# icsp.net
KiCad netlist of a schematic drawn in EAGLE
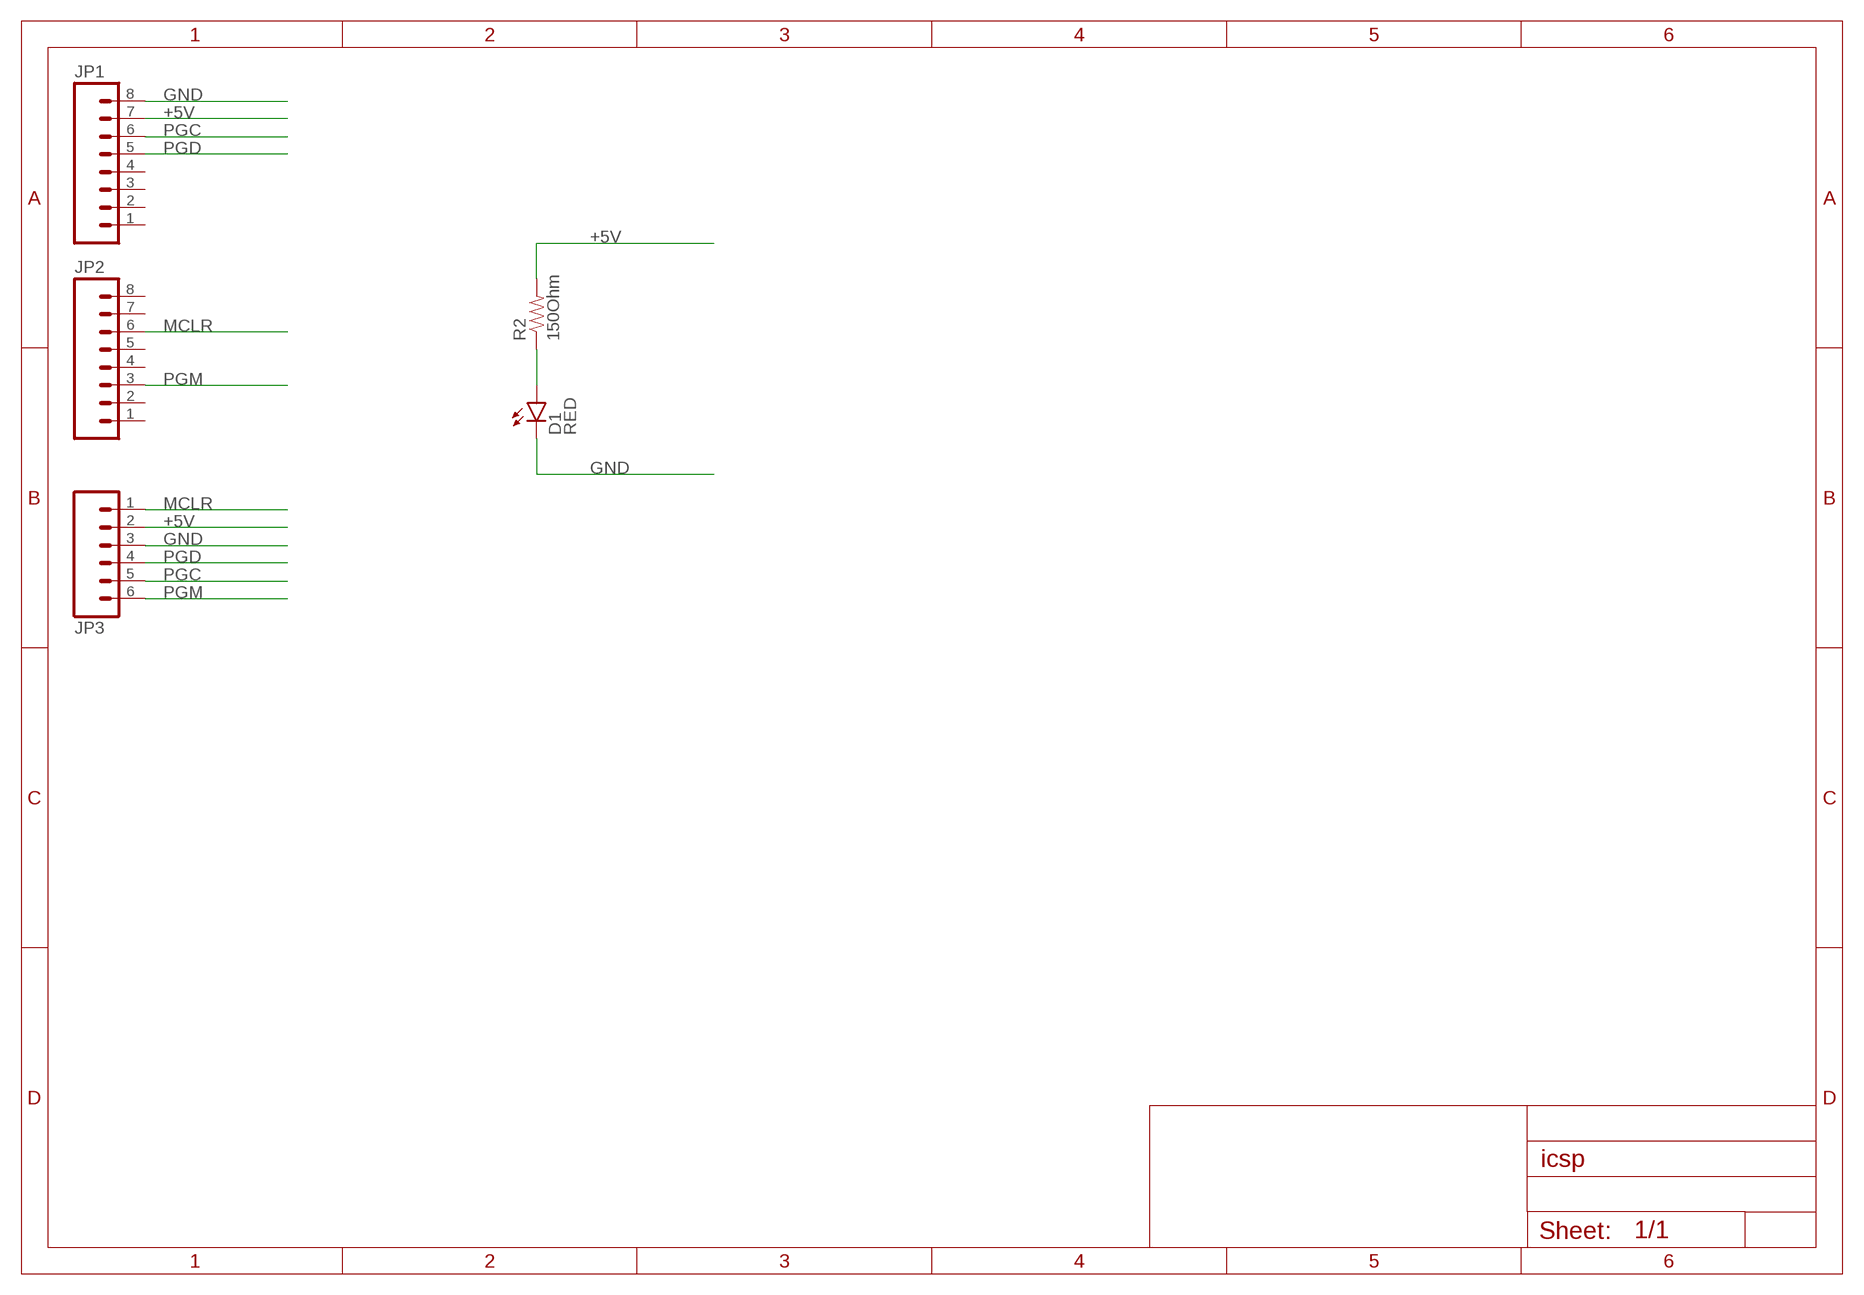
[diagram p0: schematic, sheet 1]

(export (version "E")
  (design (tool "Eeschema 10.0.6"))
  (components
    (comp (ref "D1")
      (value "RED")
      (footprint "eagle-import:LED-0603")
      (libsource (lib "eagle-import") (part "LED-RED0603"))
    )
    (comp (ref "JP1")
      (value "M081X08")
      (footprint "eagle-import:1X08")
      (libsource (lib "eagle-import") (part "M081X08"))
    )
    (comp (ref "JP2")
      (value "M081X08")
      (footprint "eagle-import:1X08")
      (libsource (lib "eagle-import") (part "M081X08"))
    )
    (comp (ref "JP3")
      (value "M06SIP_LOCK")
      (footprint "eagle-import:1X06-SIP_LOCK")
      (libsource (lib "eagle-import") (part "M06SIP_LOCK"))
    )
    (comp (ref "R2")
      (value "150Ohm")
      (footprint "eagle-import:0402-RES")
      (libsource (lib "eagle-import") (part "RESISTOR0402-RES"))
    )
  )
  (nets
    (net (code "1") (name "/+5V") (class "Default")
      (node (ref "JP1") (pin "7") (pinfunction "7_7") (pintype "passive"))
      (node (ref "JP3") (pin "2") (pinfunction "2_2") (pintype "passive"))
      (node (ref "R2") (pin "2") (pinfunction "2_2") (pintype "passive"))
    )
    (net (code "2") (name "/GND") (class "Default")
      (node (ref "D1") (pin "C") (pinfunction "C_C") (pintype "passive"))
      (node (ref "JP1") (pin "8") (pinfunction "8_8") (pintype "passive"))
      (node (ref "JP3") (pin "3") (pinfunction "3_3") (pintype "passive"))
    )
    (net (code "3") (name "/MCLR") (class "Default")
      (node (ref "JP2") (pin "6") (pinfunction "6_6") (pintype "passive"))
      (node (ref "JP3") (pin "1") (pinfunction "1_1") (pintype "passive"))
    )
    (net (code "4") (name "/PGC") (class "Default")
      (node (ref "JP1") (pin "6") (pinfunction "6_6") (pintype "passive"))
      (node (ref "JP3") (pin "5") (pinfunction "5_5") (pintype "passive"))
    )
    (net (code "5") (name "/PGD") (class "Default")
      (node (ref "JP1") (pin "5") (pinfunction "5_5") (pintype "passive"))
      (node (ref "JP3") (pin "4") (pinfunction "4_4") (pintype "passive"))
    )
    (net (code "6") (name "/PGM") (class "Default")
      (node (ref "JP2") (pin "3") (pinfunction "3_3") (pintype "passive"))
      (node (ref "JP3") (pin "6") (pinfunction "6_6") (pintype "passive"))
    )
    (net (code "7") (name "Net-(D1-PadA)") (class "Default")
      (node (ref "D1") (pin "A") (pinfunction "A_A") (pintype "passive"))
      (node (ref "R2") (pin "1") (pinfunction "1_1") (pintype "passive"))
    )
    (net (code "8") (name "unconnected-(JP1-Pad1)") (class "Default")
      (node (ref "JP1") (pin "1") (pinfunction "1_1") (pintype "passive"))
    )
    (net (code "9") (name "unconnected-(JP1-Pad2)") (class "Default")
      (node (ref "JP1") (pin "2") (pinfunction "2_2") (pintype "passive"))
    )
    (net (code "10") (name "unconnected-(JP1-Pad3)") (class "Default")
      (node (ref "JP1") (pin "3") (pinfunction "3_3") (pintype "passive"))
    )
    (net (code "11") (name "unconnected-(JP1-Pad4)") (class "Default")
      (node (ref "JP1") (pin "4") (pinfunction "4_4") (pintype "passive"))
    )
    (net (code "12") (name "unconnected-(JP2-Pad1)") (class "Default")
      (node (ref "JP2") (pin "1") (pinfunction "1_1") (pintype "passive"))
    )
    (net (code "13") (name "unconnected-(JP2-Pad2)") (class "Default")
      (node (ref "JP2") (pin "2") (pinfunction "2_2") (pintype "passive"))
    )
    (net (code "14") (name "unconnected-(JP2-Pad4)") (class "Default")
      (node (ref "JP2") (pin "4") (pinfunction "4_4") (pintype "passive"))
    )
    (net (code "15") (name "unconnected-(JP2-Pad5)") (class "Default")
      (node (ref "JP2") (pin "5") (pinfunction "5_5") (pintype "passive"))
    )
    (net (code "16") (name "unconnected-(JP2-Pad7)") (class "Default")
      (node (ref "JP2") (pin "7") (pinfunction "7_7") (pintype "passive"))
    )
    (net (code "17") (name "unconnected-(JP2-Pad8)") (class "Default")
      (node (ref "JP2") (pin "8") (pinfunction "8_8") (pintype "passive"))
    )
  )
)
